# ma8x8_interface.net
KiCad netlist of a schematic drawn in EAGLE
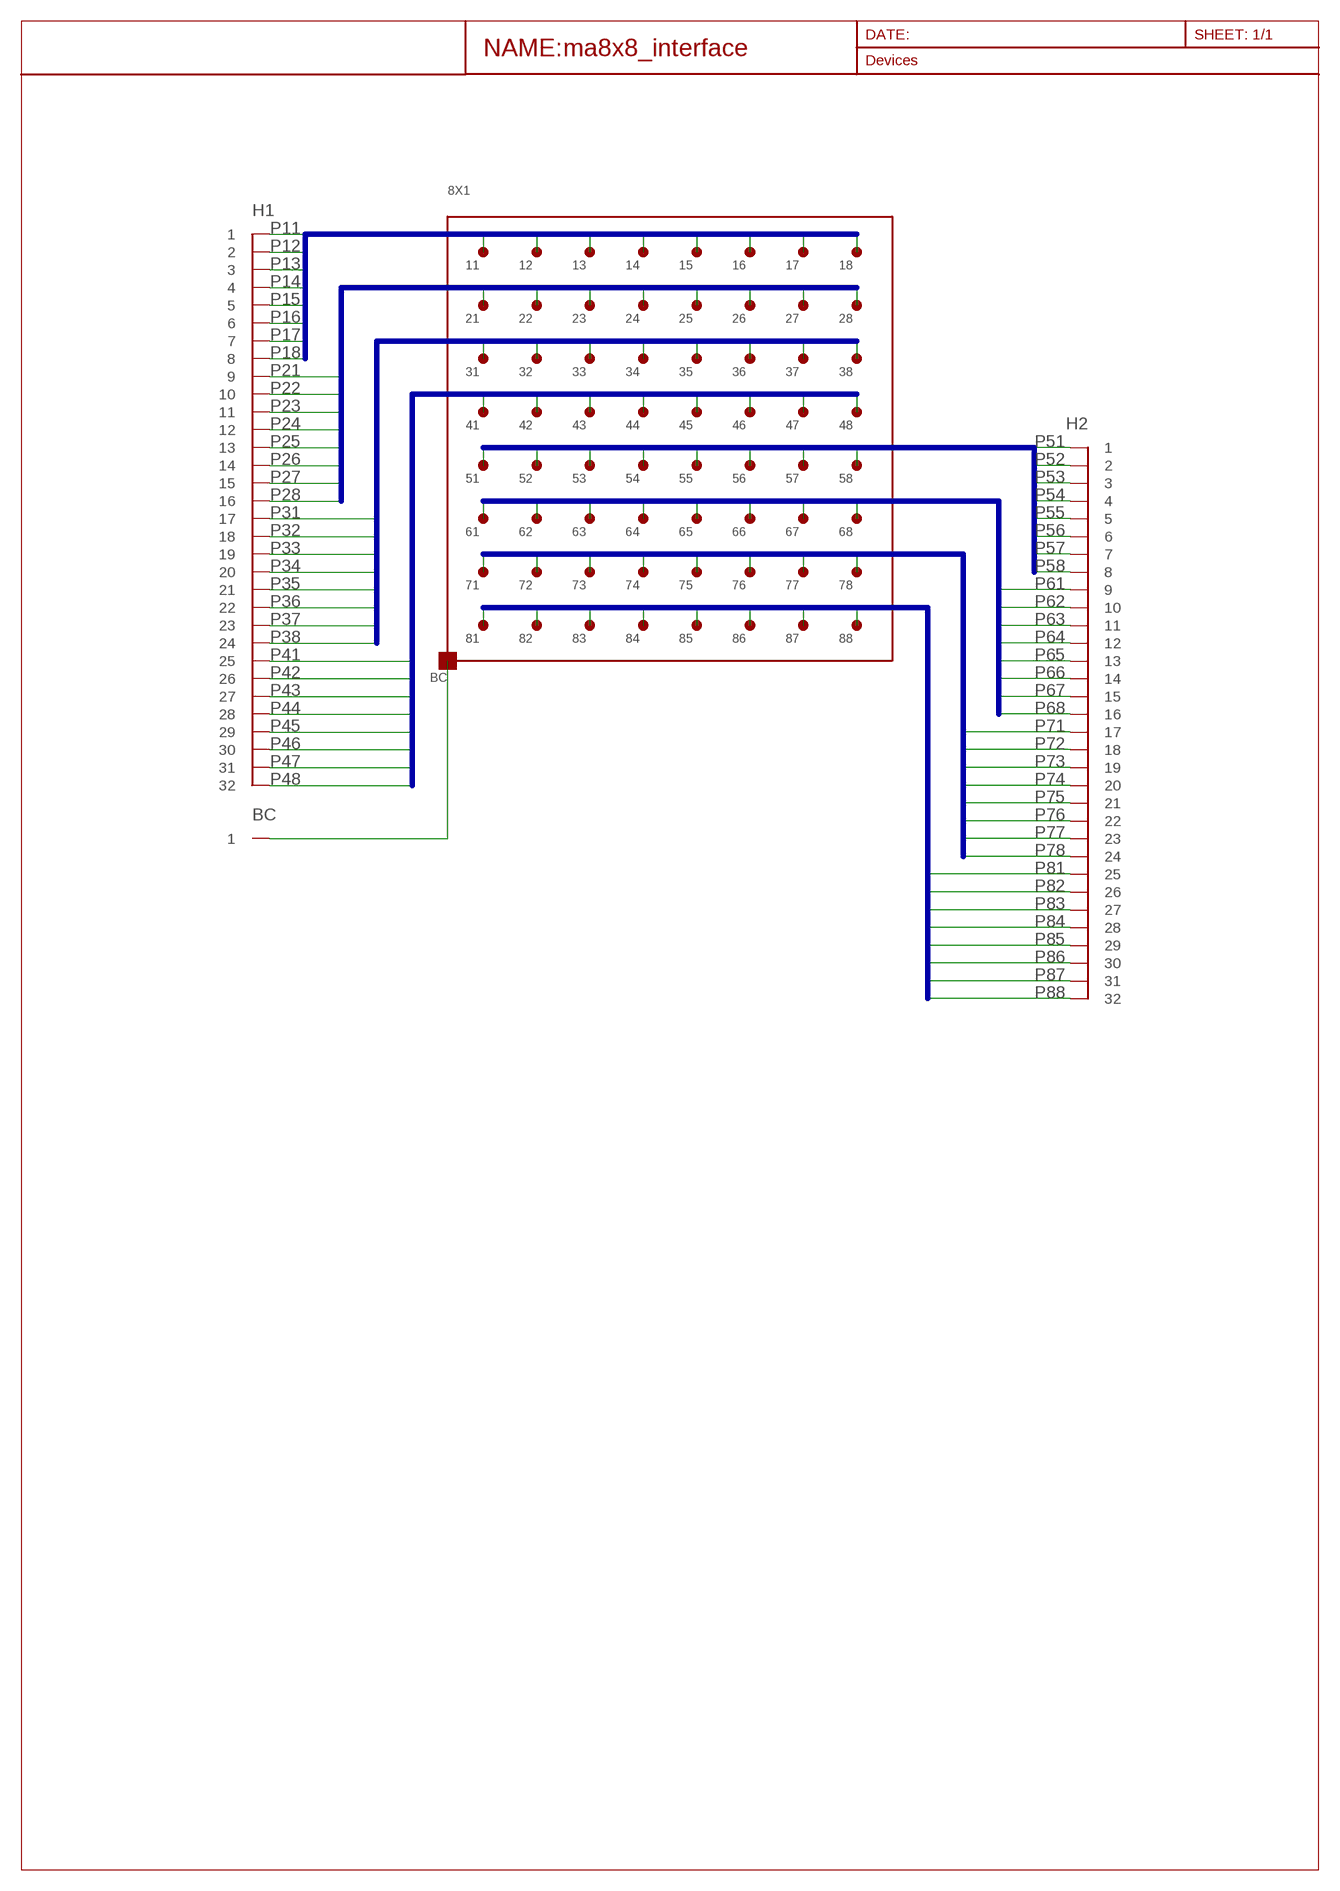
[diagram p0: schematic, sheet 1]

(export (version "E")
  (design (tool "Eeschema 10.0.6"))
  (components
    (comp (ref "8X1")
      (value "8X8-POGO")
      (footprint "eagle-import:8X8-POGO")
      (libsource (lib "eagle-import") (part "8X8-POGO"))
    )
    (comp (ref "BC")
      (value "D01-9920146")
      (footprint "eagle-import:D01-9920146")
      (libsource (lib "eagle-import") (part "D01-9920146"))
    )
    (comp (ref "H1")
      (value "D01-9923246")
      (footprint "eagle-import:D01-9923246")
      (libsource (lib "eagle-import") (part "D01-9923246"))
    )
    (comp (ref "H2")
      (value "D01-9923246")
      (footprint "eagle-import:D01-9923246")
      (libsource (lib "eagle-import") (part "D01-9923246"))
    )
  )
  (nets
    (net (code "1") (name "/P11") (class "Default")
      (node (ref "8X1") (pin "11") (pinfunction "11_11") (pintype "bidirectional"))
      (node (ref "H1") (pin "1") (pinfunction "1_1") (pintype "bidirectional"))
    )
    (net (code "2") (name "/P12") (class "Default")
      (node (ref "8X1") (pin "12") (pinfunction "12_12") (pintype "bidirectional"))
      (node (ref "H1") (pin "2") (pinfunction "2_2") (pintype "bidirectional"))
    )
    (net (code "3") (name "/P13") (class "Default")
      (node (ref "8X1") (pin "13") (pinfunction "13_13") (pintype "bidirectional"))
      (node (ref "H1") (pin "3") (pinfunction "3_3") (pintype "bidirectional"))
    )
    (net (code "4") (name "/P14") (class "Default")
      (node (ref "8X1") (pin "14") (pinfunction "14_14") (pintype "bidirectional"))
      (node (ref "H1") (pin "4") (pinfunction "4_4") (pintype "bidirectional"))
    )
    (net (code "5") (name "/P15") (class "Default")
      (node (ref "8X1") (pin "15") (pinfunction "15_15") (pintype "bidirectional"))
      (node (ref "H1") (pin "5") (pinfunction "5_5") (pintype "bidirectional"))
    )
    (net (code "6") (name "/P16") (class "Default")
      (node (ref "8X1") (pin "16") (pinfunction "16_16") (pintype "bidirectional"))
      (node (ref "H1") (pin "6") (pinfunction "6_6") (pintype "bidirectional"))
    )
    (net (code "7") (name "/P17") (class "Default")
      (node (ref "8X1") (pin "17") (pinfunction "17_17") (pintype "bidirectional"))
      (node (ref "H1") (pin "7") (pinfunction "7_7") (pintype "bidirectional"))
    )
    (net (code "8") (name "/P18") (class "Default")
      (node (ref "8X1") (pin "18") (pinfunction "18_18") (pintype "bidirectional"))
      (node (ref "H1") (pin "8") (pinfunction "8_8") (pintype "bidirectional"))
    )
    (net (code "9") (name "/P21") (class "Default")
      (node (ref "8X1") (pin "21") (pinfunction "21_21") (pintype "bidirectional"))
      (node (ref "H1") (pin "9") (pinfunction "9_9") (pintype "bidirectional"))
    )
    (net (code "10") (name "/P22") (class "Default")
      (node (ref "8X1") (pin "22") (pinfunction "22_22") (pintype "bidirectional"))
      (node (ref "H1") (pin "10") (pinfunction "10_10") (pintype "bidirectional"))
    )
    (net (code "11") (name "/P23") (class "Default")
      (node (ref "8X1") (pin "23") (pinfunction "23_23") (pintype "bidirectional"))
      (node (ref "H1") (pin "11") (pinfunction "11_11") (pintype "bidirectional"))
    )
    (net (code "12") (name "/P24") (class "Default")
      (node (ref "8X1") (pin "24") (pinfunction "24_24") (pintype "bidirectional"))
      (node (ref "H1") (pin "12") (pinfunction "12_12") (pintype "bidirectional"))
    )
    (net (code "13") (name "/P25") (class "Default")
      (node (ref "8X1") (pin "25") (pinfunction "25_25") (pintype "bidirectional"))
      (node (ref "H1") (pin "13") (pinfunction "13_13") (pintype "bidirectional"))
    )
    (net (code "14") (name "/P26") (class "Default")
      (node (ref "8X1") (pin "26") (pinfunction "26_26") (pintype "bidirectional"))
      (node (ref "H1") (pin "14") (pinfunction "14_14") (pintype "bidirectional"))
    )
    (net (code "15") (name "/P27") (class "Default")
      (node (ref "8X1") (pin "27") (pinfunction "27_27") (pintype "bidirectional"))
      (node (ref "H1") (pin "15") (pinfunction "15_15") (pintype "bidirectional"))
    )
    (net (code "16") (name "/P28") (class "Default")
      (node (ref "8X1") (pin "28") (pinfunction "28_28") (pintype "bidirectional"))
      (node (ref "H1") (pin "16") (pinfunction "16_16") (pintype "bidirectional"))
    )
    (net (code "17") (name "/P31") (class "Default")
      (node (ref "8X1") (pin "31") (pinfunction "31_31") (pintype "bidirectional"))
      (node (ref "H1") (pin "17") (pinfunction "17_17") (pintype "bidirectional"))
    )
    (net (code "18") (name "/P32") (class "Default")
      (node (ref "8X1") (pin "32") (pinfunction "32_32") (pintype "bidirectional"))
      (node (ref "H1") (pin "18") (pinfunction "18_18") (pintype "bidirectional"))
    )
    (net (code "19") (name "/P33") (class "Default")
      (node (ref "8X1") (pin "33") (pinfunction "33_33") (pintype "bidirectional"))
      (node (ref "H1") (pin "19") (pinfunction "19_19") (pintype "bidirectional"))
    )
    (net (code "20") (name "/P34") (class "Default")
      (node (ref "8X1") (pin "34") (pinfunction "34_34") (pintype "bidirectional"))
      (node (ref "H1") (pin "20") (pinfunction "20_20") (pintype "bidirectional"))
    )
    (net (code "21") (name "/P35") (class "Default")
      (node (ref "8X1") (pin "35") (pinfunction "35_35") (pintype "bidirectional"))
      (node (ref "H1") (pin "21") (pinfunction "21_21") (pintype "bidirectional"))
    )
    (net (code "22") (name "/P36") (class "Default")
      (node (ref "8X1") (pin "36") (pinfunction "36_36") (pintype "bidirectional"))
      (node (ref "H1") (pin "22") (pinfunction "22_22") (pintype "bidirectional"))
    )
    (net (code "23") (name "/P37") (class "Default")
      (node (ref "8X1") (pin "37") (pinfunction "37_37") (pintype "bidirectional"))
      (node (ref "H1") (pin "23") (pinfunction "23_23") (pintype "bidirectional"))
    )
    (net (code "24") (name "/P38") (class "Default")
      (node (ref "8X1") (pin "38") (pinfunction "38_38") (pintype "bidirectional"))
      (node (ref "H1") (pin "24") (pinfunction "24_24") (pintype "bidirectional"))
    )
    (net (code "25") (name "/P41") (class "Default")
      (node (ref "8X1") (pin "41") (pinfunction "41_41") (pintype "bidirectional"))
      (node (ref "H1") (pin "25") (pinfunction "25_25") (pintype "bidirectional"))
    )
    (net (code "26") (name "/P42") (class "Default")
      (node (ref "8X1") (pin "42") (pinfunction "42_42") (pintype "bidirectional"))
      (node (ref "H1") (pin "26") (pinfunction "26_26") (pintype "bidirectional"))
    )
    (net (code "27") (name "/P43") (class "Default")
      (node (ref "8X1") (pin "43") (pinfunction "43_43") (pintype "bidirectional"))
      (node (ref "H1") (pin "27") (pinfunction "27_27") (pintype "bidirectional"))
    )
    (net (code "28") (name "/P44") (class "Default")
      (node (ref "8X1") (pin "44") (pinfunction "44_44") (pintype "bidirectional"))
      (node (ref "H1") (pin "28") (pinfunction "28_28") (pintype "bidirectional"))
    )
    (net (code "29") (name "/P45") (class "Default")
      (node (ref "8X1") (pin "45") (pinfunction "45_45") (pintype "bidirectional"))
      (node (ref "H1") (pin "29") (pinfunction "29_29") (pintype "bidirectional"))
    )
    (net (code "30") (name "/P46") (class "Default")
      (node (ref "8X1") (pin "46") (pinfunction "46_46") (pintype "bidirectional"))
      (node (ref "H1") (pin "30") (pinfunction "30_30") (pintype "bidirectional"))
    )
    (net (code "31") (name "/P47") (class "Default")
      (node (ref "8X1") (pin "47") (pinfunction "47_47") (pintype "bidirectional"))
      (node (ref "H1") (pin "31") (pinfunction "31_31") (pintype "bidirectional"))
    )
    (net (code "32") (name "/P48") (class "Default")
      (node (ref "8X1") (pin "48") (pinfunction "48_48") (pintype "bidirectional"))
      (node (ref "H1") (pin "32") (pinfunction "32_32") (pintype "bidirectional"))
    )
    (net (code "33") (name "/P51") (class "Default")
      (node (ref "8X1") (pin "51") (pinfunction "51_51") (pintype "bidirectional"))
      (node (ref "H2") (pin "1") (pinfunction "1_1") (pintype "bidirectional"))
    )
    (net (code "34") (name "/P52") (class "Default")
      (node (ref "8X1") (pin "52") (pinfunction "52_52") (pintype "bidirectional"))
      (node (ref "H2") (pin "2") (pinfunction "2_2") (pintype "bidirectional"))
    )
    (net (code "35") (name "/P53") (class "Default")
      (node (ref "8X1") (pin "53") (pinfunction "53_53") (pintype "bidirectional"))
      (node (ref "H2") (pin "3") (pinfunction "3_3") (pintype "bidirectional"))
    )
    (net (code "36") (name "/P54") (class "Default")
      (node (ref "8X1") (pin "54") (pinfunction "54_54") (pintype "bidirectional"))
      (node (ref "H2") (pin "4") (pinfunction "4_4") (pintype "bidirectional"))
    )
    (net (code "37") (name "/P55") (class "Default")
      (node (ref "8X1") (pin "55") (pinfunction "55_55") (pintype "bidirectional"))
      (node (ref "H2") (pin "5") (pinfunction "5_5") (pintype "bidirectional"))
    )
    (net (code "38") (name "/P56") (class "Default")
      (node (ref "8X1") (pin "56") (pinfunction "56_56") (pintype "bidirectional"))
      (node (ref "H2") (pin "6") (pinfunction "6_6") (pintype "bidirectional"))
    )
    (net (code "39") (name "/P57") (class "Default")
      (node (ref "8X1") (pin "57") (pinfunction "57_57") (pintype "bidirectional"))
      (node (ref "H2") (pin "7") (pinfunction "7_7") (pintype "bidirectional"))
    )
    (net (code "40") (name "/P58") (class "Default")
      (node (ref "8X1") (pin "58") (pinfunction "58_58") (pintype "bidirectional"))
      (node (ref "H2") (pin "8") (pinfunction "8_8") (pintype "bidirectional"))
    )
    (net (code "41") (name "/P61") (class "Default")
      (node (ref "8X1") (pin "61") (pinfunction "61_61") (pintype "bidirectional"))
      (node (ref "H2") (pin "9") (pinfunction "9_9") (pintype "bidirectional"))
    )
    (net (code "42") (name "/P62") (class "Default")
      (node (ref "8X1") (pin "62") (pinfunction "62_62") (pintype "bidirectional"))
      (node (ref "H2") (pin "10") (pinfunction "10_10") (pintype "bidirectional"))
    )
    (net (code "43") (name "/P63") (class "Default")
      (node (ref "8X1") (pin "63") (pinfunction "63_63") (pintype "bidirectional"))
      (node (ref "H2") (pin "11") (pinfunction "11_11") (pintype "bidirectional"))
    )
    (net (code "44") (name "/P64") (class "Default")
      (node (ref "8X1") (pin "64") (pinfunction "64_64") (pintype "bidirectional"))
      (node (ref "H2") (pin "12") (pinfunction "12_12") (pintype "bidirectional"))
    )
    (net (code "45") (name "/P65") (class "Default")
      (node (ref "8X1") (pin "65") (pinfunction "65_65") (pintype "bidirectional"))
      (node (ref "H2") (pin "13") (pinfunction "13_13") (pintype "bidirectional"))
    )
    (net (code "46") (name "/P66") (class "Default")
      (node (ref "8X1") (pin "66") (pinfunction "66_66") (pintype "bidirectional"))
      (node (ref "H2") (pin "14") (pinfunction "14_14") (pintype "bidirectional"))
    )
    (net (code "47") (name "/P67") (class "Default")
      (node (ref "8X1") (pin "67") (pinfunction "67_67") (pintype "bidirectional"))
      (node (ref "H2") (pin "15") (pinfunction "15_15") (pintype "bidirectional"))
    )
    (net (code "48") (name "/P68") (class "Default")
      (node (ref "8X1") (pin "68") (pinfunction "68_68") (pintype "bidirectional"))
      (node (ref "H2") (pin "16") (pinfunction "16_16") (pintype "bidirectional"))
    )
    (net (code "49") (name "/P71") (class "Default")
      (node (ref "8X1") (pin "71") (pinfunction "71_71") (pintype "bidirectional"))
      (node (ref "H2") (pin "17") (pinfunction "17_17") (pintype "bidirectional"))
    )
    (net (code "50") (name "/P72") (class "Default")
      (node (ref "8X1") (pin "72") (pinfunction "72_72") (pintype "bidirectional"))
      (node (ref "H2") (pin "18") (pinfunction "18_18") (pintype "bidirectional"))
    )
    (net (code "51") (name "/P73") (class "Default")
      (node (ref "8X1") (pin "73") (pinfunction "73_73") (pintype "bidirectional"))
      (node (ref "H2") (pin "19") (pinfunction "19_19") (pintype "bidirectional"))
    )
    (net (code "52") (name "/P74") (class "Default")
      (node (ref "8X1") (pin "74") (pinfunction "74_74") (pintype "bidirectional"))
      (node (ref "H2") (pin "20") (pinfunction "20_20") (pintype "bidirectional"))
    )
    (net (code "53") (name "/P75") (class "Default")
      (node (ref "8X1") (pin "75") (pinfunction "75_75") (pintype "bidirectional"))
      (node (ref "H2") (pin "21") (pinfunction "21_21") (pintype "bidirectional"))
    )
    (net (code "54") (name "/P76") (class "Default")
      (node (ref "8X1") (pin "76") (pinfunction "76_76") (pintype "bidirectional"))
      (node (ref "H2") (pin "22") (pinfunction "22_22") (pintype "bidirectional"))
    )
    (net (code "55") (name "/P77") (class "Default")
      (node (ref "8X1") (pin "77") (pinfunction "77_77") (pintype "bidirectional"))
      (node (ref "H2") (pin "23") (pinfunction "23_23") (pintype "bidirectional"))
    )
    (net (code "56") (name "/P78") (class "Default")
      (node (ref "8X1") (pin "78") (pinfunction "78_78") (pintype "bidirectional"))
      (node (ref "H2") (pin "24") (pinfunction "24_24") (pintype "bidirectional"))
    )
    (net (code "57") (name "/P81") (class "Default")
      (node (ref "8X1") (pin "81") (pinfunction "81_81") (pintype "bidirectional"))
      (node (ref "H2") (pin "25") (pinfunction "25_25") (pintype "bidirectional"))
    )
    (net (code "58") (name "/P82") (class "Default")
      (node (ref "8X1") (pin "82") (pinfunction "82_82") (pintype "bidirectional"))
      (node (ref "H2") (pin "26") (pinfunction "26_26") (pintype "bidirectional"))
    )
    (net (code "59") (name "/P83") (class "Default")
      (node (ref "8X1") (pin "83") (pinfunction "83_83") (pintype "bidirectional"))
      (node (ref "H2") (pin "27") (pinfunction "27_27") (pintype "bidirectional"))
    )
    (net (code "60") (name "/P84") (class "Default")
      (node (ref "8X1") (pin "84") (pinfunction "84_84") (pintype "bidirectional"))
      (node (ref "H2") (pin "28") (pinfunction "28_28") (pintype "bidirectional"))
    )
    (net (code "61") (name "/P85") (class "Default")
      (node (ref "8X1") (pin "85") (pinfunction "85_85") (pintype "bidirectional"))
      (node (ref "H2") (pin "29") (pinfunction "29_29") (pintype "bidirectional"))
    )
    (net (code "62") (name "/P86") (class "Default")
      (node (ref "8X1") (pin "86") (pinfunction "86_86") (pintype "bidirectional"))
      (node (ref "H2") (pin "30") (pinfunction "30_30") (pintype "bidirectional"))
    )
    (net (code "63") (name "/P87") (class "Default")
      (node (ref "8X1") (pin "87") (pinfunction "87_87") (pintype "bidirectional"))
      (node (ref "H2") (pin "31") (pinfunction "31_31") (pintype "bidirectional"))
    )
    (net (code "64") (name "/P88") (class "Default")
      (node (ref "8X1") (pin "88") (pinfunction "88_88") (pintype "bidirectional"))
      (node (ref "H2") (pin "32") (pinfunction "32_32") (pintype "bidirectional"))
    )
    (net (code "65") (name "Net-(8X1-B-PadB1)") (class "Default")
      (node (ref "8X1") (pin "B1") (pinfunction "B_B1") (pintype "bidirectional"))
      (node (ref "8X1") (pin "B2") (pinfunction "B_B2") (pintype "bidirectional"))
      (node (ref "8X1") (pin "B3") (pinfunction "B_B3") (pintype "bidirectional"))
      (node (ref "8X1") (pin "B4") (pinfunction "B_B4") (pintype "bidirectional"))
      (node (ref "8X1") (pin "B5") (pinfunction "B_B5") (pintype "bidirectional"))
      (node (ref "8X1") (pin "B6") (pinfunction "B_B6") (pintype "bidirectional"))
      (node (ref "8X1") (pin "B7") (pinfunction "B_B7") (pintype "bidirectional"))
      (node (ref "8X1") (pin "B8") (pinfunction "B_B8") (pintype "bidirectional"))
      (node (ref "BC") (pin "1") (pinfunction "1_1") (pintype "bidirectional"))
    )
  )
)
